# connections.net
KiCad netlist of a schematic drawn in Altium Designer
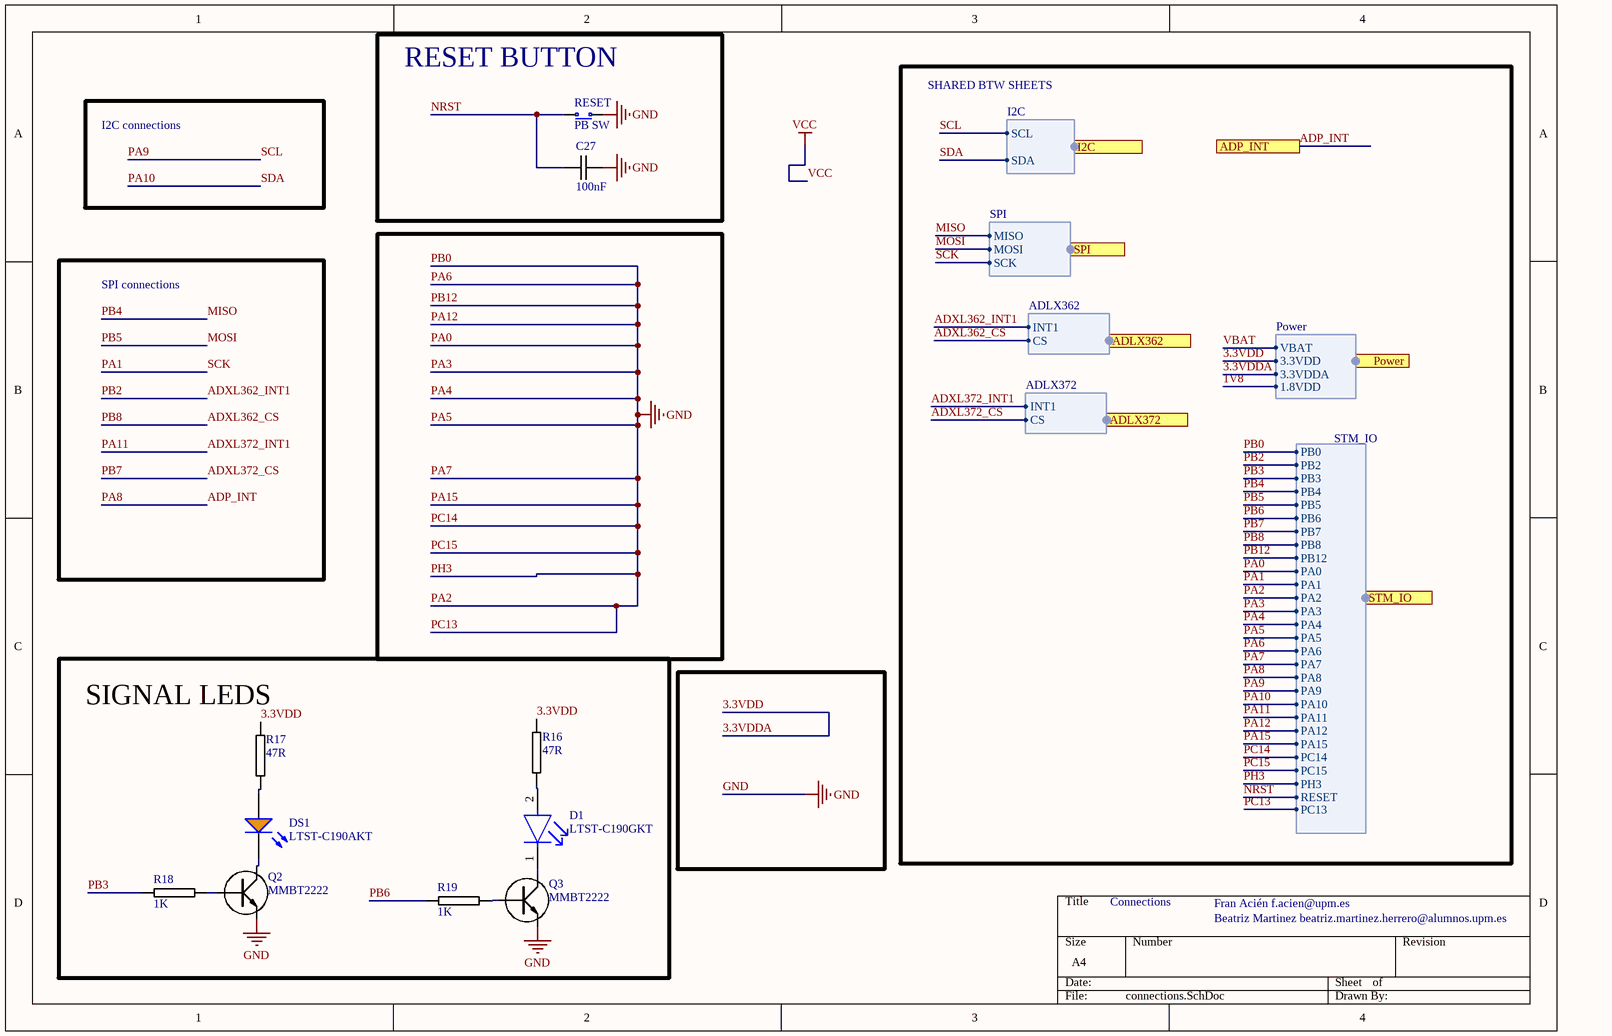
[diagram p0: connections.SchDoc]

(export (version "E")
  (design (tool "Eeschema 10.0.6"))
  (components
    (comp (ref "C27")
      (value "100nF")
      (footprint "0603C-GENERIC")
      (description "CAPACITOR 0603 CERAMIC")
      (fields (field (name "TOLERANCE") "±10%") (field (name "MANUFACTURER PART NUMBER") "C1608X7R1H103K"))
      (libsource (lib "vh_altium_library") (part "0603C-100NF-50V-X7R-TDK"))
    )
    (comp (ref "D1")
      (value "LTST-C190GKT")
      (footprint "FP-LTST-C190GKT-MFG")
      (description "LED GREEN CLEAR CHIP SMD")
      (fields (field (name "VOLTAGE") "2V"))
      (libsource (lib "Altium Content Vault") (part "8706943c75ba83719d021d2fdc84c58"))
    )
    (comp (ref "DS1")
      (value "LTST-C190AKT")
      (footprint "LTST-C190AKT-2_V")
      (description "Single Color Chip LED, 2.1 V, 2 mcd, -55 to 85 degC, 2-Pin SMD, RoHS, Tape and Reel")
      (libsource (lib "Altium Content Vault") (part "LED-ORANGE-AK-2"))
    )
    (comp (ref "Q2")
      (value "MMBT2222")
      (footprint "SOT23-BCE")
      (description "BC847 SMALL SIGNAL NPN TRANSISTOR")
      (libsource (lib "vh_altium_library") (part "MMBT2222"))
    )
    (comp (ref "Q3")
      (value "MMBT2222")
      (footprint "SOT23-BCE")
      (description "BC847 SMALL SIGNAL NPN TRANSISTOR")
      (libsource (lib "vh_altium_library") (part "MMBT2222"))
    )
    (comp (ref "R16")
      (value "47R")
      (footprint "0603R-47")
      (description "GENERIC RESISTOR 0603")
      (fields
        (field (name "MANUFACTURER PART NUMBER") "RMC 1/16 47 1% R")
        (field (name "MANUFACTURER") "Stackpole Electronics Inc")
      )
      (libsource (lib "vh_altium_library") (part "0603R-47R"))
    )
    (comp (ref "R17")
      (value "47R")
      (footprint "0603R-47")
      (description "GENERIC RESISTOR 0603")
      (fields
        (field (name "MANUFACTURER PART NUMBER") "RMC 1/16 47 1% R")
        (field (name "MANUFACTURER") "Stackpole Electronics Inc")
      )
      (libsource (lib "vh_altium_library") (part "0603R-47R"))
    )
    (comp (ref "R18")
      (value "1K")
      (footprint "0603R-1k")
      (description "GENERIC RESISTOR 0603")
      (fields
        (field (name "MANUFACTURER PART NUMBER") "RMCF 1/16 1K 1% R")
        (field (name "MANUFACTURER") "Stackpole Electronics Inc")
      )
      (libsource (lib "vh_altium_library") (part "0603R-1K"))
    )
    (comp (ref "R19")
      (value "1K")
      (footprint "0603R-1k")
      (description "GENERIC RESISTOR 0603")
      (fields
        (field (name "MANUFACTURER PART NUMBER") "RMCF 1/16 1K 1% R")
        (field (name "MANUFACTURER") "Stackpole Electronics Inc")
      )
      (libsource (lib "vh_altium_library") (part "0603R-1K"))
    )
    (comp (ref "RESET")
      (value "PB SW")
      (footprint "Switch-PB-6.2x6.3mm-SMD")
      (description "Tactile Switch, SPNO, SMD, 160gf, 6.2x6.3x2.5mm")
      (fields
        (field (name "PART NUMBER") "Switch-PB-6.2x6.3mm-SMD")
        (field (name "MANUFACTURER") "Dailywell")
        (field (name "PUBLISHER") "Nordic Semiconductor")
      )
      (libsource (lib "FEEL2020") (part "TS604VM1-025BR-R"))
    )
  )
  (nets
    (net (code "8") (name "/3.3VDD") (class "Default")
      (node (ref "R16") (pin "1") (pintype "passive"))
      (node (ref "R17") (pin "2") (pintype "passive"))
    )
    (net (code "16") (name "/NRST") (class "Default")
      (node (ref "C27") (pin "1") (pintype "passive"))
      (node (ref "RESET") (pin "1") (pinfunction "N.O_1") (pintype "passive"))
    )
    (net (code "20") (name "/PB3") (class "Default") (node (ref "R18") (pin "1") (pintype "passive")))
    (net (code "21") (name "/PB6") (class "Default") (node (ref "R19") (pin "1") (pintype "passive")))
    (net (code "29") (name "GND") (class "Default")
      (node (ref "C27") (pin "2") (pintype "passive"))
      (node (ref "Q2") (pin "E") (pintype "passive"))
      (node (ref "Q3") (pin "E") (pintype "passive"))
      (node (ref "RESET") (pin "2") (pinfunction "COM_2") (pintype "passive"))
    )
    (net (code "30") (name "Net-(D1-A)") (class "Default")
      (node (ref "D1") (pin "2") (pinfunction "A_2") (pintype "passive"))
      (node (ref "R16") (pin "2") (pintype "passive"))
    )
    (net (code "31") (name "Net-(D1-C)") (class "Default")
      (node (ref "D1") (pin "1") (pinfunction "C_1") (pintype "passive"))
      (node (ref "Q3") (pin "C") (pintype "passive"))
    )
    (net (code "32") (name "Net-(DS1-A)") (class "Default")
      (node (ref "DS1") (pin "1") (pinfunction "A_1") (pintype "passive"))
      (node (ref "R17") (pin "1") (pintype "passive"))
    )
    (net (code "33") (name "Net-(DS1-K)") (class "Default")
      (node (ref "DS1") (pin "2") (pinfunction "K_2") (pintype "passive"))
      (node (ref "Q2") (pin "C") (pintype "passive"))
    )
    (net (code "34") (name "Net-(Q2-PadB)") (class "Default")
      (node (ref "Q2") (pin "B") (pintype "passive"))
      (node (ref "R18") (pin "2") (pintype "passive"))
    )
    (net (code "35") (name "Net-(Q3-PadB)") (class "Default")
      (node (ref "Q3") (pin "B") (pintype "passive"))
      (node (ref "R19") (pin "2") (pintype "passive"))
    )
  )
)
